# Edzzanine_Console_Basic.net
KiCad netlist of a schematic drawn in EAGLE
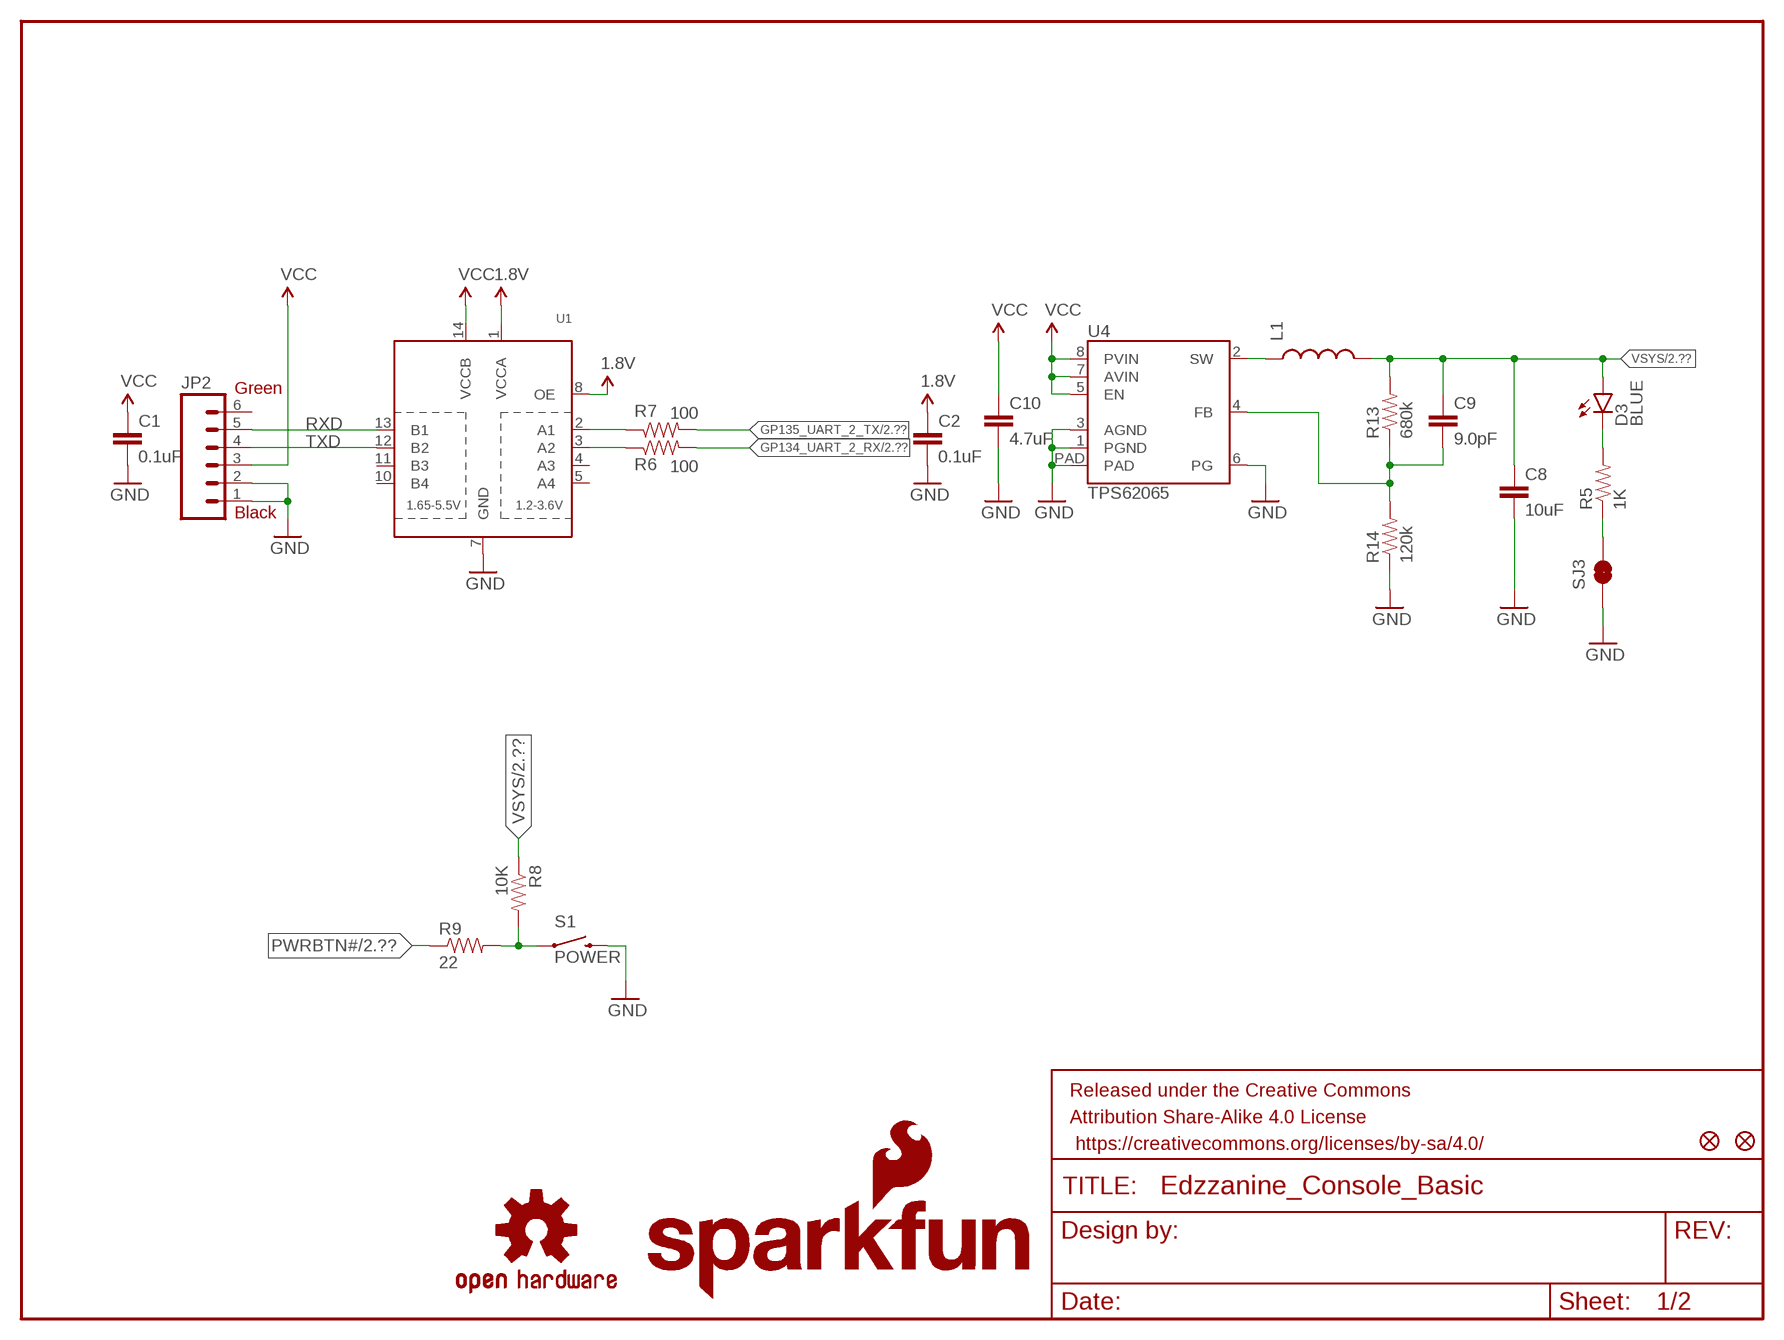
[diagram p0: schematic, sheet 1]
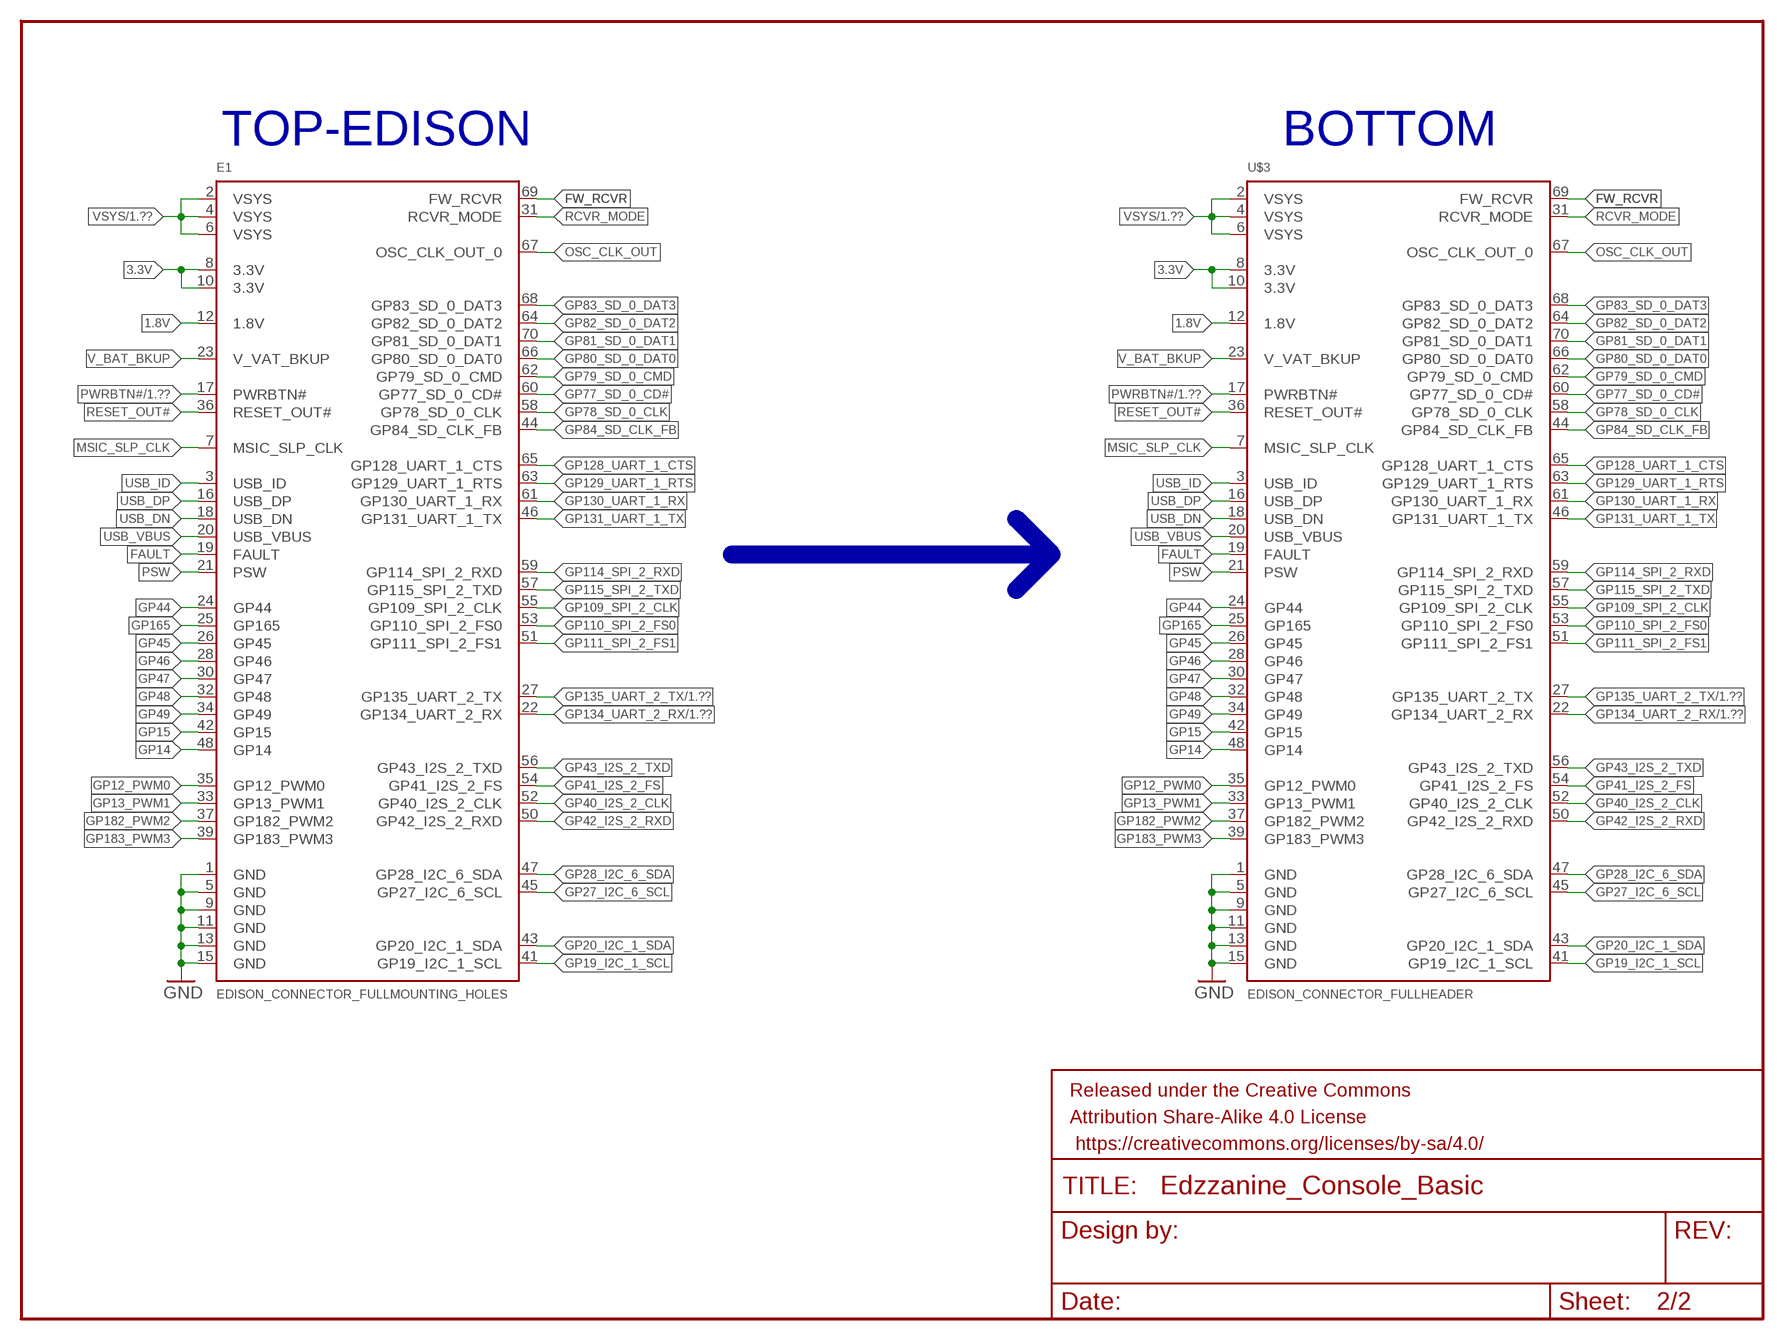
[diagram p1: schematic, sheet 2]

(export (version "E")
  (design (tool "Eeschema 10.0.6"))
  (components
    (comp (ref "C1")
      (value "0.1uF")
      (footprint "eagle-import:0603-CAP")
      (libsource (lib "eagle-import") (part "0.1UF-25V(+80/-20%)(0603)"))
    )
    (comp (ref "C2")
      (value "0.1uF")
      (footprint "eagle-import:0603-CAP")
      (libsource (lib "eagle-import") (part "0.1UF-25V(+80/-20%)(0603)"))
    )
    (comp (ref "C8")
      (value "10uF")
      (footprint "eagle-import:1206")
      (libsource (lib "eagle-import") (part "10UF-6.3V-20%(1206)"))
    )
    (comp (ref "C9")
      (value "9.0pF")
      (footprint "eagle-import:0603-CAP")
      (libsource (lib "eagle-import") (part "9.0PF-50V-10%(0603)"))
    )
    (comp (ref "C10")
      (value "4.7uF")
      (footprint "eagle-import:0603-CAP")
      (libsource (lib "eagle-import") (part "4.7UF-6.3V-10%(0603)0603"))
    )
    (comp (ref "D3")
      (value "BLUE")
      (footprint "eagle-import:LED-0603")
      (libsource (lib "eagle-import") (part "LED-BLUE0603"))
    )
    (comp (ref "FID1")
      (value "FIDUCIAL1X2")
      (footprint "eagle-import:FIDUCIAL-1X2")
      (libsource (lib "eagle-import") (part "FIDUCIAL1X2"))
    )
    (comp (ref "FID2")
      (value "FIDUCIAL1X2")
      (footprint "eagle-import:FIDUCIAL-1X2")
      (libsource (lib "eagle-import") (part "FIDUCIAL1X2"))
    )
    (comp (ref "FRAME1")
      (value "FRAME-LETTER")
      (footprint "eagle-import:CREATIVE_COMMONS")
      (libsource (lib "eagle-import") (part "FRAME-LETTER"))
    )
    (comp (ref "JP2")
      (value "M06SMD")
      (footprint "eagle-import:1X06-SMD")
      (libsource (lib "eagle-import") (part "M06SMD"))
    )
    (comp (ref "L1")
      (value "INDUCTOR")
      (footprint "eagle-import:INDUCTOR-SRP4020")
      (libsource (lib "eagle-import") (part "INDUCTOR"))
    )
    (comp (ref "LOGO1")
      (value "SFE_LOGO_NAME_FLAME.1_INCH")
      (footprint "eagle-import:SFE_LOGO_NAME_FLAME_.1")
      (libsource (lib "eagle-import") (part "SFE_LOGO_NAME_FLAME.1_INCH"))
    )
    (comp (ref "LOGO4")
      (value "OSHW-LOGOS")
      (footprint "eagle-import:OSHW-LOGO-S")
      (libsource (lib "eagle-import") (part "OSHW-LOGOS"))
    )
    (comp (ref "R5")
      (value "1K")
      (footprint "eagle-import:0603-RES")
      (libsource (lib "eagle-import") (part "1KOHM1/10W1%(0603)"))
    )
    (comp (ref "R6")
      (value "100")
      (footprint "eagle-import:0603-RES")
      (libsource (lib "eagle-import") (part "100OHM1/10W1%(0603)"))
    )
    (comp (ref "R7")
      (value "100")
      (footprint "eagle-import:0603-RES")
      (libsource (lib "eagle-import") (part "100OHM1/10W1%(0603)"))
    )
    (comp (ref "R8")
      (value "10K")
      (footprint "eagle-import:0603-RES")
      (libsource (lib "eagle-import") (part "10KOHM1/10W1%(0603)0603"))
    )
    (comp (ref "R9")
      (value "22")
      (footprint "eagle-import:0603-RES")
      (libsource (lib "eagle-import") (part "22OHM1/10W1%(0603)"))
    )
    (comp (ref "R13")
      (value "680k")
      (footprint "eagle-import:0603-RES")
      (libsource (lib "eagle-import") (part "RESISTOR0603"))
    )
    (comp (ref "R14")
      (value "120k")
      (footprint "eagle-import:0603-RES")
      (libsource (lib "eagle-import") (part "RESISTOR0603"))
    )
    (comp (ref "S1")
      (value "POWER")
      (footprint "eagle-import:TACTILE-SWITCH-1101NE")
      (libsource (lib "eagle-import") (part "SWITCH-MOMENTARY-2-SMD-1101NE"))
    )
    (comp (ref "SJ3")
      (value "JUMPER-PAD-2-NC_BY_TRACE")
      (footprint "eagle-import:PAD-JUMPER-2-NC_BY_TRACE_YES_SILK")
      (libsource (lib "eagle-import") (part "JUMPER-PAD-2-NC_BY_TRACE"))
    )
    (comp (ref "U1")
      (value "TXB0104PWRSOIC14")
      (footprint "eagle-import:SO14")
      (libsource (lib "eagle-import") (part "TXB0104PWRSOIC14"))
    )
    (comp (ref "U4")
      (value "TPS62065")
      (footprint "eagle-import:WSON-8-PAD")
      (libsource (lib "eagle-import") (part "TPS62065"))
    )
    (comp (ref "E1")
      (value "EDISON_CONNECTOR_FULLMOUNTING_HOLES")
      (footprint "eagle-import:EDISON_DAUGHTER")
      (libsource (lib "eagle-import") (part "EDISON_CONNECTOR_FULLMOUNTING_HOLES"))
    )
    (comp (ref "FRAME2")
      (value "FRAME-LETTER")
      (footprint "eagle-import:CREATIVE_COMMONS")
      (libsource (lib "eagle-import") (part "FRAME-LETTER"))
    )
    (comp (ref "U$3")
      (value "EDISON_CONNECTOR_FULLHEADER")
      (footprint "eagle-import:DF40C-70DP-0.4(51)")
      (libsource (lib "eagle-import") (part "EDISON_CONNECTOR_FULLHEADER"))
    )
  )
  (nets
    (net (code "1") (name "1.8V") (class "Default")
      (node (ref "C2") (pin "1") (pinfunction "1_1") (pintype "passive"))
      (node (ref "E1") (pin "12") (pinfunction "1.8V_12") (pintype "bidirectional"))
      (node (ref "U$3") (pin "12") (pinfunction "1.8V_12") (pintype "bidirectional"))
      (node (ref "U1") (pin "1") (pinfunction "VCCA_1") (pintype "bidirectional"))
      (node (ref "U1") (pin "8") (pinfunction "OE_8") (pintype "bidirectional"))
    )
    (net (code "2") (name "3.3V") (class "Default")
      (node (ref "E1") (pin "10") (pinfunction "3.3V_10") (pintype "bidirectional"))
      (node (ref "E1") (pin "8") (pinfunction "3.3V_8") (pintype "bidirectional"))
      (node (ref "U$3") (pin "10") (pinfunction "3.3V_10") (pintype "bidirectional"))
      (node (ref "U$3") (pin "8") (pinfunction "3.3V_8") (pintype "bidirectional"))
    )
    (net (code "3") (name "FAULT") (class "Default")
      (node (ref "E1") (pin "19") (pinfunction "FAULT_19") (pintype "bidirectional"))
      (node (ref "U$3") (pin "19") (pinfunction "FAULT_19") (pintype "bidirectional"))
    )
    (net (code "4") (name "FW_RCVR") (class "Default")
      (node (ref "E1") (pin "69") (pinfunction "FW_RCVR_69") (pintype "bidirectional"))
      (node (ref "U$3") (pin "69") (pinfunction "FW_RCVR_69") (pintype "bidirectional"))
    )
    (net (code "5") (name "GND") (class "Default")
      (node (ref "C1") (pin "2") (pinfunction "2_2") (pintype "passive"))
      (node (ref "C10") (pin "2") (pinfunction "2_2") (pintype "passive"))
      (node (ref "C2") (pin "2") (pinfunction "2_2") (pintype "passive"))
      (node (ref "C8") (pin "2") (pinfunction "2_2") (pintype "passive"))
      (node (ref "E1") (pin "1") (pinfunction "GND_1") (pintype "bidirectional"))
      (node (ref "E1") (pin "11") (pinfunction "GND_11") (pintype "bidirectional"))
      (node (ref "E1") (pin "13") (pinfunction "GND_13") (pintype "bidirectional"))
      (node (ref "E1") (pin "15") (pinfunction "GND_15") (pintype "bidirectional"))
      (node (ref "E1") (pin "5") (pinfunction "GND_5") (pintype "bidirectional"))
      (node (ref "E1") (pin "9") (pinfunction "GND_9") (pintype "bidirectional"))
      (node (ref "JP2") (pin "1") (pinfunction "1_1") (pintype "passive"))
      (node (ref "JP2") (pin "2") (pinfunction "2_2") (pintype "passive"))
      (node (ref "R14") (pin "1") (pinfunction "1_1") (pintype "passive"))
      (node (ref "S1") (pin "P$2") (pinfunction "2_P$2") (pintype "passive"))
      (node (ref "SJ3") (pin "1") (pinfunction "1_1") (pintype "passive"))
      (node (ref "U$3") (pin "1") (pinfunction "GND_1") (pintype "bidirectional"))
      (node (ref "U$3") (pin "11") (pinfunction "GND_11") (pintype "bidirectional"))
      (node (ref "U$3") (pin "13") (pinfunction "GND_13") (pintype "bidirectional"))
      (node (ref "U$3") (pin "15") (pinfunction "GND_15") (pintype "bidirectional"))
      (node (ref "U$3") (pin "5") (pinfunction "GND_5") (pintype "bidirectional"))
      (node (ref "U$3") (pin "9") (pinfunction "GND_9") (pintype "bidirectional"))
      (node (ref "U1") (pin "7") (pinfunction "GND_7") (pintype "bidirectional"))
      (node (ref "U4") (pin "1") (pinfunction "PGND_1") (pintype "bidirectional"))
      (node (ref "U4") (pin "3") (pinfunction "AGND_3") (pintype "bidirectional"))
      (node (ref "U4") (pin "6") (pinfunction "PG_6") (pintype "bidirectional"))
      (node (ref "U4") (pin "PAD") (pinfunction "PAD_PAD") (pintype "bidirectional"))
    )
    (net (code "6") (name "GP12_PWM0") (class "Default")
      (node (ref "E1") (pin "35") (pinfunction "GP12_PWM0_35") (pintype "bidirectional"))
      (node (ref "U$3") (pin "35") (pinfunction "GP12_PWM0_35") (pintype "bidirectional"))
    )
    (net (code "7") (name "GP13_PWM1") (class "Default")
      (node (ref "E1") (pin "33") (pinfunction "GP13_PWM1_33") (pintype "bidirectional"))
      (node (ref "U$3") (pin "33") (pinfunction "GP13_PWM1_33") (pintype "bidirectional"))
    )
    (net (code "8") (name "GP14") (class "Default")
      (node (ref "E1") (pin "48") (pinfunction "GP14_48") (pintype "bidirectional"))
      (node (ref "U$3") (pin "48") (pinfunction "GP14_48") (pintype "bidirectional"))
    )
    (net (code "9") (name "GP15") (class "Default")
      (node (ref "E1") (pin "42") (pinfunction "GP15_42") (pintype "bidirectional"))
      (node (ref "U$3") (pin "42") (pinfunction "GP15_42") (pintype "bidirectional"))
    )
    (net (code "10") (name "GP19_I2C_1_SCL") (class "Default")
      (node (ref "E1") (pin "41") (pinfunction "GP19_I2C_1_SCL_41") (pintype "bidirectional"))
      (node (ref "U$3") (pin "41") (pinfunction "GP19_I2C_1_SCL_41") (pintype "bidirectional"))
    )
    (net (code "11") (name "GP20_I2C_1_SDA") (class "Default")
      (node (ref "E1") (pin "43") (pinfunction "GP20_I2C_1_SDA_43") (pintype "bidirectional"))
      (node (ref "U$3") (pin "43") (pinfunction "GP20_I2C_1_SDA_43") (pintype "bidirectional"))
    )
    (net (code "12") (name "GP27_I2C_6_SCL") (class "Default")
      (node (ref "E1") (pin "45") (pinfunction "GP27_I2C_6_SCL_45") (pintype "bidirectional"))
      (node (ref "U$3") (pin "45") (pinfunction "GP27_I2C_6_SCL_45") (pintype "bidirectional"))
    )
    (net (code "13") (name "GP28_I2C_6_SDA") (class "Default")
      (node (ref "E1") (pin "47") (pinfunction "GP28_I2C_6_SDA_47") (pintype "bidirectional"))
      (node (ref "U$3") (pin "47") (pinfunction "GP28_I2C_6_SDA_47") (pintype "bidirectional"))
    )
    (net (code "14") (name "GP40_I2S_2_CLK") (class "Default")
      (node (ref "E1") (pin "52") (pinfunction "GP40_I2S_2_CLK_52") (pintype "bidirectional"))
      (node (ref "U$3") (pin "52") (pinfunction "GP40_I2S_2_CLK_52") (pintype "bidirectional"))
    )
    (net (code "15") (name "GP41_I2S_2_FS") (class "Default")
      (node (ref "E1") (pin "54") (pinfunction "GP41_I2S_2_FS_54") (pintype "bidirectional"))
      (node (ref "U$3") (pin "54") (pinfunction "GP41_I2S_2_FS_54") (pintype "bidirectional"))
    )
    (net (code "16") (name "GP42_I2S_2_RXD") (class "Default")
      (node (ref "E1") (pin "50") (pinfunction "GP42_I2S_2_RXD_50") (pintype "bidirectional"))
      (node (ref "U$3") (pin "50") (pinfunction "GP42_I2S_2_RXD_50") (pintype "bidirectional"))
    )
    (net (code "17") (name "GP43_I2S_2_TXD") (class "Default")
      (node (ref "E1") (pin "56") (pinfunction "GP43_I2S_2_TXD_56") (pintype "bidirectional"))
      (node (ref "U$3") (pin "56") (pinfunction "GP43_I2S_2_TXD_56") (pintype "bidirectional"))
    )
    (net (code "18") (name "GP44") (class "Default")
      (node (ref "E1") (pin "24") (pinfunction "GP44_24") (pintype "bidirectional"))
      (node (ref "U$3") (pin "24") (pinfunction "GP44_24") (pintype "bidirectional"))
    )
    (net (code "19") (name "GP45") (class "Default")
      (node (ref "E1") (pin "26") (pinfunction "GP45_26") (pintype "bidirectional"))
      (node (ref "U$3") (pin "26") (pinfunction "GP45_26") (pintype "bidirectional"))
    )
    (net (code "20") (name "GP46") (class "Default")
      (node (ref "E1") (pin "28") (pinfunction "GP46_28") (pintype "bidirectional"))
      (node (ref "U$3") (pin "28") (pinfunction "GP46_28") (pintype "bidirectional"))
    )
    (net (code "21") (name "GP47") (class "Default")
      (node (ref "E1") (pin "30") (pinfunction "GP47_30") (pintype "bidirectional"))
      (node (ref "U$3") (pin "30") (pinfunction "GP47_30") (pintype "bidirectional"))
    )
    (net (code "22") (name "GP48") (class "Default")
      (node (ref "E1") (pin "32") (pinfunction "GP48_32") (pintype "bidirectional"))
      (node (ref "U$3") (pin "32") (pinfunction "GP48_32") (pintype "bidirectional"))
    )
    (net (code "23") (name "GP49") (class "Default")
      (node (ref "E1") (pin "34") (pinfunction "GP49_34") (pintype "bidirectional"))
      (node (ref "U$3") (pin "34") (pinfunction "GP49_34") (pintype "bidirectional"))
    )
    (net (code "24") (name "GP77_SD_0_CD#") (class "Default")
      (node (ref "E1") (pin "60") (pinfunction "GP77_SD_0_CD#_60") (pintype "bidirectional"))
      (node (ref "U$3") (pin "60") (pinfunction "GP77_SD_0_CD#_60") (pintype "bidirectional"))
    )
    (net (code "25") (name "GP78_SD_0_CLK") (class "Default")
      (node (ref "E1") (pin "58") (pinfunction "GP78_SD_0_CLK_58") (pintype "bidirectional"))
      (node (ref "U$3") (pin "58") (pinfunction "GP78_SD_0_CLK_58") (pintype "bidirectional"))
    )
    (net (code "26") (name "GP79_SD_0_CMD") (class "Default")
      (node (ref "E1") (pin "62") (pinfunction "GP79_SD_0_CMD_62") (pintype "bidirectional"))
      (node (ref "U$3") (pin "62") (pinfunction "GP79_SD_0_CMD_62") (pintype "bidirectional"))
    )
    (net (code "27") (name "GP80_SD_0_DAT0") (class "Default")
      (node (ref "E1") (pin "66") (pinfunction "GP80_SD_0_DAT0_66") (pintype "bidirectional"))
      (node (ref "U$3") (pin "66") (pinfunction "GP80_SD_0_DAT0_66") (pintype "bidirectional"))
    )
    (net (code "28") (name "GP81_SD_0_DAT1") (class "Default")
      (node (ref "E1") (pin "70") (pinfunction "GP81_SD_0_DAT1_70") (pintype "bidirectional"))
      (node (ref "U$3") (pin "70") (pinfunction "GP81_SD_0_DAT1_70") (pintype "bidirectional"))
    )
    (net (code "29") (name "GP82_SD_0_DAT2") (class "Default")
      (node (ref "E1") (pin "64") (pinfunction "GP82_SD_0_DAT2_64") (pintype "bidirectional"))
      (node (ref "U$3") (pin "64") (pinfunction "GP82_SD_0_DAT2_64") (pintype "bidirectional"))
    )
    (net (code "30") (name "GP83_SD_0_DAT3") (class "Default")
      (node (ref "E1") (pin "68") (pinfunction "GP83_SD_0_DAT3_68") (pintype "bidirectional"))
      (node (ref "U$3") (pin "68") (pinfunction "GP83_SD_0_DAT3_68") (pintype "bidirectional"))
    )
    (net (code "31") (name "GP84_SD_CLK_FB") (class "Default")
      (node (ref "E1") (pin "44") (pinfunction "GP84_SD_CLK_FB_44") (pintype "bidirectional"))
      (node (ref "U$3") (pin "44") (pinfunction "GP84_SD_CLK_FB_44") (pintype "bidirectional"))
    )
    (net (code "32") (name "GP109_SPI_2_CLK") (class "Default")
      (node (ref "E1") (pin "55") (pinfunction "GP109_SPI_2_CLK_55") (pintype "bidirectional"))
      (node (ref "U$3") (pin "55") (pinfunction "GP109_SPI_2_CLK_55") (pintype "bidirectional"))
    )
    (net (code "33") (name "GP110_SPI_2_FS0") (class "Default")
      (node (ref "E1") (pin "53") (pinfunction "GP110_SPI_2_FS0_53") (pintype "bidirectional"))
      (node (ref "U$3") (pin "53") (pinfunction "GP110_SPI_2_FS0_53") (pintype "bidirectional"))
    )
    (net (code "34") (name "GP111_SPI_2_FS1") (class "Default")
      (node (ref "E1") (pin "51") (pinfunction "GP111_SPI_2_FS1_51") (pintype "bidirectional"))
      (node (ref "U$3") (pin "51") (pinfunction "GP111_SPI_2_FS1_51") (pintype "bidirectional"))
    )
    (net (code "35") (name "GP114_SPI_2_RXD") (class "Default")
      (node (ref "E1") (pin "59") (pinfunction "GP114_SPI_2_RXD_59") (pintype "bidirectional"))
      (node (ref "U$3") (pin "59") (pinfunction "GP114_SPI_2_RXD_59") (pintype "bidirectional"))
    )
    (net (code "36") (name "GP115_SPI_2_TXD") (class "Default")
      (node (ref "E1") (pin "57") (pinfunction "GP115_SPI_2_TXD_57") (pintype "bidirectional"))
      (node (ref "U$3") (pin "57") (pinfunction "GP115_SPI_2_TXD_57") (pintype "bidirectional"))
    )
    (net (code "37") (name "GP128_UART_1_CTS") (class "Default")
      (node (ref "E1") (pin "65") (pinfunction "GP128_UART_1_CTS_65") (pintype "bidirectional"))
      (node (ref "U$3") (pin "65") (pinfunction "GP128_UART_1_CTS_65") (pintype "bidirectional"))
    )
    (net (code "38") (name "GP129_UART_1_RTS") (class "Default")
      (node (ref "E1") (pin "63") (pinfunction "GP129_UART_1_RTS_63") (pintype "bidirectional"))
      (node (ref "U$3") (pin "63") (pinfunction "GP129_UART_1_RTS_63") (pintype "bidirectional"))
    )
    (net (code "39") (name "GP130_UART_1_RX") (class "Default")
      (node (ref "E1") (pin "61") (pinfunction "GP130_UART_1_RX_61") (pintype "bidirectional"))
      (node (ref "U$3") (pin "61") (pinfunction "GP130_UART_1_RX_61") (pintype "bidirectional"))
    )
    (net (code "40") (name "GP131_UART_1_TX") (class "Default")
      (node (ref "E1") (pin "46") (pinfunction "GP131_UART_1_TX_46") (pintype "bidirectional"))
      (node (ref "U$3") (pin "46") (pinfunction "GP131_UART_1_TX_46") (pintype "bidirectional"))
    )
    (net (code "41") (name "GP134_UART_2_RX") (class "Default")
      (node (ref "E1") (pin "22") (pinfunction "GP134_UART_2_RX_22") (pintype "bidirectional"))
      (node (ref "R6") (pin "2") (pinfunction "2_2") (pintype "passive"))
      (node (ref "U$3") (pin "22") (pinfunction "GP134_UART_2_RX_22") (pintype "bidirectional"))
    )
    (net (code "42") (name "GP135_UART_2_TX") (class "Default")
      (node (ref "E1") (pin "27") (pinfunction "GP135_UART_2_TX_27") (pintype "bidirectional"))
      (node (ref "R7") (pin "2") (pinfunction "2_2") (pintype "passive"))
      (node (ref "U$3") (pin "27") (pinfunction "GP135_UART_2_TX_27") (pintype "bidirectional"))
    )
    (net (code "43") (name "GP165") (class "Default")
      (node (ref "E1") (pin "25") (pinfunction "GP165_25") (pintype "bidirectional"))
      (node (ref "U$3") (pin "25") (pinfunction "GP165_25") (pintype "bidirectional"))
    )
    (net (code "44") (name "GP182_PWM2") (class "Default")
      (node (ref "E1") (pin "37") (pinfunction "GP182_PWM2_37") (pintype "bidirectional"))
      (node (ref "U$3") (pin "37") (pinfunction "GP182_PWM2_37") (pintype "bidirectional"))
    )
    (net (code "45") (name "GP183_PWM3") (class "Default")
      (node (ref "E1") (pin "39") (pinfunction "GP183_PWM3_39") (pintype "bidirectional"))
      (node (ref "U$3") (pin "39") (pinfunction "GP183_PWM3_39") (pintype "bidirectional"))
    )
    (net (code "46") (name "MSIC_SLP_CLK") (class "Default")
      (node (ref "E1") (pin "7") (pinfunction "MSIC_SLP_CLK_7") (pintype "bidirectional"))
      (node (ref "U$3") (pin "7") (pinfunction "MSIC_SLP_CLK_7") (pintype "bidirectional"))
    )
    (net (code "47") (name "Net-(D3-PadC)") (class "Default")
      (node (ref "D3") (pin "C") (pinfunction "C_C") (pintype "passive"))
      (node (ref "R5") (pin "2") (pinfunction "2_2") (pintype "passive"))
    )
    (net (code "48") (name "Net-(L1-1)") (class "Default")
      (node (ref "L1") (pin "P$1") (pinfunction "1_P$1") (pintype "passive"))
      (node (ref "U4") (pin "2") (pinfunction "SW_2") (pintype "bidirectional"))
    )
    (net (code "49") (name "Net-(R5-Pad1)") (class "Default")
      (node (ref "R5") (pin "1") (pinfunction "1_1") (pintype "passive"))
      (node (ref "SJ3") (pin "2") (pinfunction "2_2") (pintype "passive"))
    )
    (net (code "50") (name "Net-(S1-1)") (class "Default")
      (node (ref "R8") (pin "2") (pinfunction "2_2") (pintype "passive"))
      (node (ref "R9") (pin "2") (pinfunction "2_2") (pintype "passive"))
      (node (ref "S1") (pin "P$1") (pinfunction "1_P$1") (pintype "passive"))
    )
    (net (code "51") (name "Net-(U1-A1)") (class "Default")
      (node (ref "R7") (pin "1") (pinfunction "1_1") (pintype "passive"))
      (node (ref "U1") (pin "2") (pinfunction "A1_2") (pintype "bidirectional"))
    )
    (net (code "52") (name "Net-(U1-A2)") (class "Default")
      (node (ref "R6") (pin "1") (pinfunction "1_1") (pintype "passive"))
      (node (ref "U1") (pin "3") (pinfunction "A2_3") (pintype "bidirectional"))
    )
    (net (code "53") (name "Net-(U4-FB)") (class "Default")
      (node (ref "C9") (pin "2") (pinfunction "2_2") (pintype "passive"))
      (node (ref "R13") (pin "1") (pinfunction "1_1") (pintype "passive"))
      (node (ref "R14") (pin "2") (pinfunction "2_2") (pintype "passive"))
      (node (ref "U4") (pin "4") (pinfunction "FB_4") (pintype "bidirectional"))
    )
    (net (code "54") (name "OSC_CLK_OUT") (class "Default")
      (node (ref "E1") (pin "67") (pinfunction "OSC_CLK_OUT_0_67") (pintype "bidirectional"))
      (node (ref "U$3") (pin "67") (pinfunction "OSC_CLK_OUT_0_67") (pintype "bidirectional"))
    )
    (net (code "55") (name "PSW") (class "Default")
      (node (ref "E1") (pin "21") (pinfunction "PSW_21") (pintype "bidirectional"))
      (node (ref "U$3") (pin "21") (pinfunction "PSW_21") (pintype "bidirectional"))
    )
    (net (code "56") (name "PWRBTN#") (class "Default")
      (node (ref "E1") (pin "17") (pinfunction "PWRBTN#_17") (pintype "bidirectional"))
      (node (ref "R9") (pin "1") (pinfunction "1_1") (pintype "passive"))
      (node (ref "U$3") (pin "17") (pinfunction "PWRBTN#_17") (pintype "bidirectional"))
    )
    (net (code "57") (name "RCVR_MODE") (class "Default")
      (node (ref "E1") (pin "31") (pinfunction "RCVR_MODE_31") (pintype "bidirectional"))
      (node (ref "U$3") (pin "31") (pinfunction "RCVR_MODE_31") (pintype "bidirectional"))
    )
    (net (code "58") (name "RESET_OUT#") (class "Default")
      (node (ref "E1") (pin "36") (pinfunction "RESET_OUT#_36") (pintype "bidirectional"))
      (node (ref "U$3") (pin "36") (pinfunction "RESET_OUT#_36") (pintype "bidirectional"))
    )
    (net (code "59") (name "RXD") (class "Default")
      (node (ref "JP2") (pin "5") (pinfunction "5_5") (pintype "passive"))
      (node (ref "U1") (pin "13") (pinfunction "B1_13") (pintype "bidirectional"))
    )
    (net (code "60") (name "TXD") (class "Default")
      (node (ref "JP2") (pin "4") (pinfunction "4_4") (pintype "passive"))
      (node (ref "U1") (pin "12") (pinfunction "B2_12") (pintype "bidirectional"))
    )
    (net (code "61") (name "USB_DN") (class "Default")
      (node (ref "E1") (pin "18") (pinfunction "USB_DN_18") (pintype "bidirectional"))
      (node (ref "U$3") (pin "18") (pinfunction "USB_DN_18") (pintype "bidirectional"))
    )
    (net (code "62") (name "USB_DP") (class "Default")
      (node (ref "E1") (pin "16") (pinfunction "USB_DP_16") (pintype "bidirectional"))
      (node (ref "U$3") (pin "16") (pinfunction "USB_DP_16") (pintype "bidirectional"))
    )
    (net (code "63") (name "USB_ID") (class "Default")
      (node (ref "E1") (pin "3") (pinfunction "USB_ID_3") (pintype "bidirectional"))
      (node (ref "U$3") (pin "3") (pinfunction "USB_ID_3") (pintype "bidirectional"))
    )
    (net (code "64") (name "USB_VBUS") (class "Default")
      (node (ref "E1") (pin "20") (pinfunction "USB_VBUS_20") (pintype "bidirectional"))
      (node (ref "U$3") (pin "20") (pinfunction "USB_VBUS_20") (pintype "bidirectional"))
    )
    (net (code "65") (name "VCC") (class "Default")
      (node (ref "C1") (pin "1") (pinfunction "1_1") (pintype "passive"))
      (node (ref "C10") (pin "1") (pinfunction "1_1") (pintype "passive"))
      (node (ref "JP2") (pin "3") (pinfunction "3_3") (pintype "passive"))
      (node (ref "U1") (pin "14") (pinfunction "VCCB_14") (pintype "bidirectional"))
      (node (ref "U4") (pin "5") (pinfunction "EN_5") (pintype "bidirectional"))
      (node (ref "U4") (pin "7") (pinfunction "AVIN_7") (pintype "bidirectional"))
      (node (ref "U4") (pin "8") (pinfunction "PVIN_8") (pintype "bidirectional"))
    )
    (net (code "66") (name "VSYS") (class "Default")
      (node (ref "C8") (pin "1") (pinfunction "1_1") (pintype "passive"))
      (node (ref "C9") (pin "1") (pinfunction "1_1") (pintype "passive"))
      (node (ref "D3") (pin "A") (pinfunction "A_A") (pintype "passive"))
      (node (ref "E1") (pin "2") (pinfunction "VSYS_2") (pintype "bidirectional"))
      (node (ref "E1") (pin "4") (pinfunction "VSYS_4") (pintype "bidirectional"))
      (node (ref "E1") (pin "6") (pinfunction "VSYS_6") (pintype "bidirectional"))
      (node (ref "L1") (pin "P$2") (pinfunction "2_P$2") (pintype "passive"))
      (node (ref "R13") (pin "2") (pinfunction "2_2") (pintype "passive"))
      (node (ref "R8") (pin "1") (pinfunction "1_1") (pintype "passive"))
      (node (ref "U$3") (pin "2") (pinfunction "VSYS_2") (pintype "bidirectional"))
      (node (ref "U$3") (pin "4") (pinfunction "VSYS_4") (pintype "bidirectional"))
      (node (ref "U$3") (pin "6") (pinfunction "VSYS_6") (pintype "bidirectional"))
    )
    (net (code "67") (name "V_BAT_BKUP") (class "Default")
      (node (ref "E1") (pin "23") (pinfunction "V_VAT_BKUP_23") (pintype "bidirectional"))
      (node (ref "U$3") (pin "23") (pinfunction "V_VAT_BKUP_23") (pintype "bidirectional"))
    )
    (net (code "68") (name "unconnected-(JP2-Pad6)") (class "Default")
      (node (ref "JP2") (pin "6") (pinfunction "6_6") (pintype "passive"))
    )
    (net (code "69") (name "unconnected-(U1-A3-Pad4)") (class "Default")
      (node (ref "U1") (pin "4") (pinfunction "A3_4") (pintype "bidirectional"))
    )
    (net (code "70") (name "unconnected-(U1-A4-Pad5)") (class "Default")
      (node (ref "U1") (pin "5") (pinfunction "A4_5") (pintype "bidirectional"))
    )
    (net (code "71") (name "unconnected-(U1-B3-Pad11)") (class "Default")
      (node (ref "U1") (pin "11") (pinfunction "B3_11") (pintype "bidirectional"))
    )
    (net (code "72") (name "unconnected-(U1-B4-Pad10)") (class "Default")
      (node (ref "U1") (pin "10") (pinfunction "B4_10") (pintype "bidirectional"))
    )
  )
)
